# t84.net
KiCad netlist of a schematic drawn in EAGLE
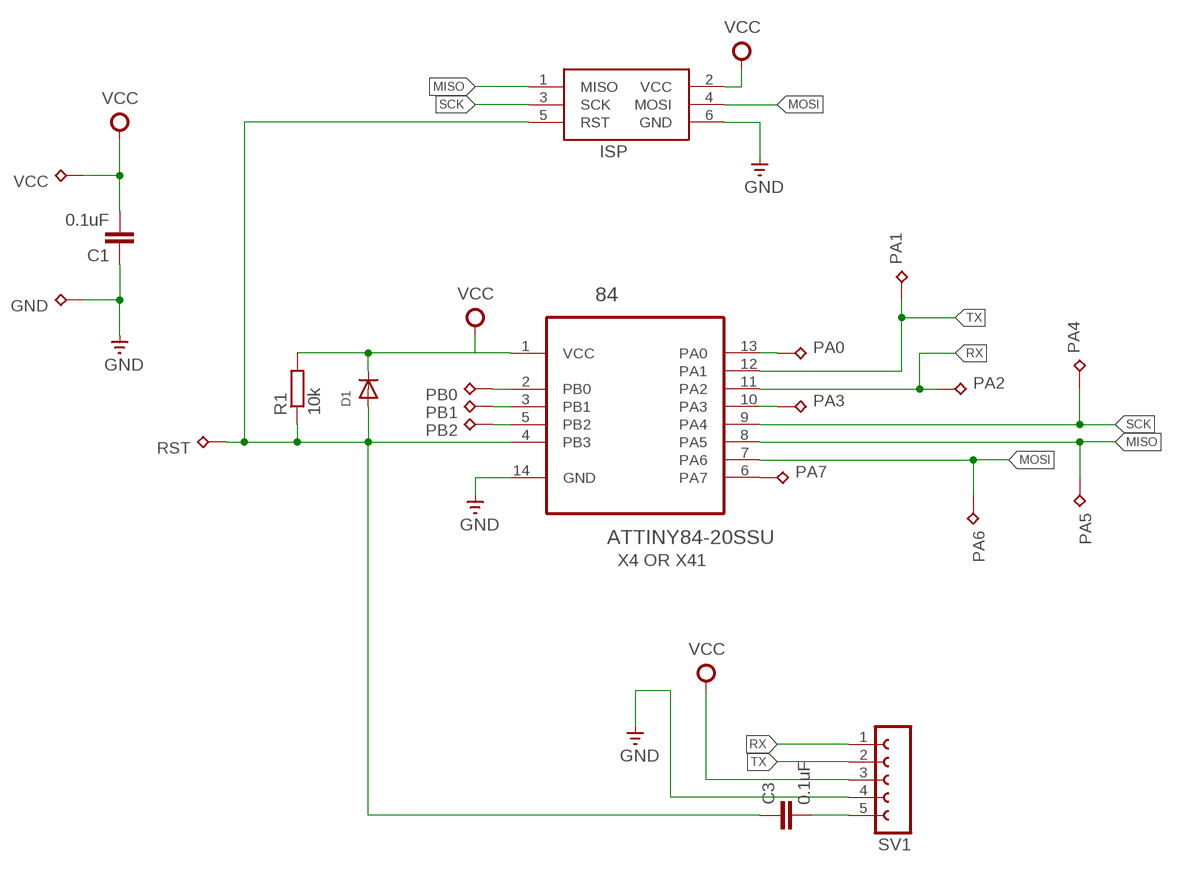
[diagram p0: schematic, sheet 1]

(export (version "E")
  (design (tool "Eeschema 10.0.6"))
  (components
    (comp (ref "84")
      (value "ATTINY84-20SSU")
      (footprint "eagle-import:SOIC127P600X175-14N")
      (libsource (lib "eagle-import") (part "ATTINY84-20SSU"))
    )
    (comp (ref "C1")
      (value "0.1uF")
      (footprint "eagle-import:C0805K")
      (libsource (lib "eagle-import") (part "C-EUC0805K"))
    )
    (comp (ref "C3")
      (value "0.1uF")
      (footprint "eagle-import:C0805K")
      (libsource (lib "eagle-import") (part "C-EUC0805K"))
    )
    (comp (ref "D1")
      (value "DIODESOD-123")
      (footprint "eagle-import:SOD-123")
      (libsource (lib "eagle-import") (part "DIODESOD-123"))
    )
    (comp (ref "GND")
      (value "1XPIN-HEADER")
      (footprint "eagle-import:1XPIN-HEADER")
      (libsource (lib "eagle-import") (part "1XPIN-HEADER"))
    )
    (comp (ref "ISP")
      (value "AVRISP-6")
      (footprint "eagle-import:AVRISP")
      (libsource (lib "eagle-import") (part "AVRISP-6"))
    )
    (comp (ref "PA0")
      (value "1XPIN-HEADER")
      (footprint "eagle-import:1XPIN-HEADER")
      (libsource (lib "eagle-import") (part "1XPIN-HEADER"))
    )
    (comp (ref "PA1")
      (value "1XPIN-HEADER")
      (footprint "eagle-import:1XPIN-HEADER")
      (libsource (lib "eagle-import") (part "1XPIN-HEADER"))
    )
    (comp (ref "PA2")
      (value "1XPIN-HEADER")
      (footprint "eagle-import:1XPIN-HEADER")
      (libsource (lib "eagle-import") (part "1XPIN-HEADER"))
    )
    (comp (ref "PA3")
      (value "1XPIN-HEADER")
      (footprint "eagle-import:1XPIN-HEADER")
      (libsource (lib "eagle-import") (part "1XPIN-HEADER"))
    )
    (comp (ref "PA4")
      (value "1XPIN-HEADER")
      (footprint "eagle-import:1XPIN-HEADER")
      (libsource (lib "eagle-import") (part "1XPIN-HEADER"))
    )
    (comp (ref "PA5")
      (value "1XPIN-HEADER")
      (footprint "eagle-import:1XPIN-HEADER")
      (libsource (lib "eagle-import") (part "1XPIN-HEADER"))
    )
    (comp (ref "PA6")
      (value "1XPIN-HEADER")
      (footprint "eagle-import:1XPIN-HEADER")
      (libsource (lib "eagle-import") (part "1XPIN-HEADER"))
    )
    (comp (ref "PA7")
      (value "1XPIN-HEADER")
      (footprint "eagle-import:1XPIN-HEADER")
      (libsource (lib "eagle-import") (part "1XPIN-HEADER"))
    )
    (comp (ref "PB0")
      (value "1XPIN-HEADER")
      (footprint "eagle-import:1XPIN-HEADER")
      (libsource (lib "eagle-import") (part "1XPIN-HEADER"))
    )
    (comp (ref "PB1")
      (value "1XPIN-HEADER")
      (footprint "eagle-import:1XPIN-HEADER")
      (libsource (lib "eagle-import") (part "1XPIN-HEADER"))
    )
    (comp (ref "PB2")
      (value "1XPIN-HEADER")
      (footprint "eagle-import:1XPIN-HEADER")
      (libsource (lib "eagle-import") (part "1XPIN-HEADER"))
    )
    (comp (ref "R1")
      (value "10k")
      (footprint "eagle-import:M0805")
      (libsource (lib "eagle-import") (part "R-EU_M0805"))
    )
    (comp (ref "RST")
      (value "1XPIN-HEADER")
      (footprint "eagle-import:1XPIN-HEADER")
      (libsource (lib "eagle-import") (part "1XPIN-HEADER"))
    )
    (comp (ref "SV1")
      (value "FE05-1")
      (footprint "eagle-import:FE05-1")
      (libsource (lib "eagle-import") (part "FE05-1"))
    )
    (comp (ref "VCC")
      (value "1XPIN-HEADER")
      (footprint "eagle-import:1XPIN-HEADER")
      (libsource (lib "eagle-import") (part "1XPIN-HEADER"))
    )
  )
  (nets
    (net (code "1") (name "GND") (class "Default")
      (node (ref "84") (pin "14") (pinfunction "GND_14") (pintype "passive"))
      (node (ref "C1") (pin "1") (pinfunction "1_1") (pintype "passive"))
      (node (ref "GND") (pin "P$1") (pinfunction "P$1_P$1") (pintype "bidirectional"))
      (node (ref "ISP") (pin "6") (pinfunction "GND_6") (pintype "power_in"))
      (node (ref "SV1") (pin "4") (pinfunction "4_4") (pintype "passive"))
    )
    (net (code "2") (name "MISO") (class "Default")
      (node (ref "84") (pin "8") (pinfunction "PA5_8") (pintype "bidirectional"))
      (node (ref "ISP") (pin "1") (pinfunction "MISO_1") (pintype "input"))
      (node (ref "PA5") (pin "P$1") (pinfunction "P$1_P$1") (pintype "bidirectional"))
    )
    (net (code "3") (name "MOSI") (class "Default")
      (node (ref "84") (pin "7") (pinfunction "PA6_7") (pintype "bidirectional"))
      (node (ref "ISP") (pin "4") (pinfunction "MOSI_4") (pintype "output"))
      (node (ref "PA6") (pin "P$1") (pinfunction "P$1_P$1") (pintype "bidirectional"))
    )
    (net (code "4") (name "Net-(84-PA0)") (class "Default")
      (node (ref "84") (pin "13") (pinfunction "PA0_13") (pintype "bidirectional"))
      (node (ref "PA0") (pin "P$1") (pinfunction "P$1_P$1") (pintype "bidirectional"))
    )
    (net (code "5") (name "Net-(84-PA3)") (class "Default")
      (node (ref "84") (pin "10") (pinfunction "PA3_10") (pintype "bidirectional"))
      (node (ref "PA3") (pin "P$1") (pinfunction "P$1_P$1") (pintype "bidirectional"))
    )
    (net (code "6") (name "Net-(84-PA7)") (class "Default")
      (node (ref "84") (pin "6") (pinfunction "PA7_6") (pintype "bidirectional"))
      (node (ref "PA7") (pin "P$1") (pinfunction "P$1_P$1") (pintype "bidirectional"))
    )
    (net (code "7") (name "Net-(84-PB0)") (class "Default")
      (node (ref "84") (pin "2") (pinfunction "PB0_2") (pintype "bidirectional"))
      (node (ref "PB0") (pin "P$1") (pinfunction "P$1_P$1") (pintype "bidirectional"))
    )
    (net (code "8") (name "Net-(84-PB1)") (class "Default")
      (node (ref "84") (pin "3") (pinfunction "PB1_3") (pintype "bidirectional"))
      (node (ref "PB1") (pin "P$1") (pinfunction "P$1_P$1") (pintype "bidirectional"))
    )
    (net (code "9") (name "Net-(84-PB2)") (class "Default")
      (node (ref "84") (pin "5") (pinfunction "PB2_5") (pintype "bidirectional"))
      (node (ref "PB2") (pin "P$1") (pinfunction "P$1_P$1") (pintype "bidirectional"))
    )
    (net (code "10") (name "Net-(84-PB3)") (class "Default")
      (node (ref "84") (pin "4") (pinfunction "PB3_4") (pintype "bidirectional"))
      (node (ref "C3") (pin "1") (pinfunction "1_1") (pintype "passive"))
      (node (ref "D1") (pin "A") (pinfunction "A_A") (pintype "passive"))
      (node (ref "ISP") (pin "5") (pinfunction "RST_5") (pintype "output"))
      (node (ref "R1") (pin "1") (pinfunction "1_1") (pintype "passive"))
      (node (ref "RST") (pin "P$1") (pinfunction "P$1_P$1") (pintype "bidirectional"))
    )
    (net (code "11") (name "Net-(C3-Pad2)") (class "Default")
      (node (ref "C3") (pin "2") (pinfunction "2_2") (pintype "passive"))
      (node (ref "SV1") (pin "5") (pinfunction "5_5") (pintype "passive"))
    )
    (net (code "12") (name "RX") (class "Default")
      (node (ref "84") (pin "11") (pinfunction "PA2_11") (pintype "bidirectional"))
      (node (ref "PA2") (pin "P$1") (pinfunction "P$1_P$1") (pintype "bidirectional"))
      (node (ref "SV1") (pin "1") (pinfunction "1_1") (pintype "passive"))
    )
    (net (code "13") (name "SCK") (class "Default")
      (node (ref "84") (pin "9") (pinfunction "PA4_9") (pintype "bidirectional"))
      (node (ref "ISP") (pin "3") (pinfunction "SCK_3") (pintype "output"))
      (node (ref "PA4") (pin "P$1") (pinfunction "P$1_P$1") (pintype "bidirectional"))
    )
    (net (code "14") (name "TX") (class "Default")
      (node (ref "84") (pin "12") (pinfunction "PA1_12") (pintype "bidirectional"))
      (node (ref "PA1") (pin "P$1") (pinfunction "P$1_P$1") (pintype "bidirectional"))
      (node (ref "SV1") (pin "2") (pinfunction "2_2") (pintype "passive"))
    )
    (net (code "15") (name "VCC") (class "Default")
      (node (ref "84") (pin "1") (pinfunction "VCC_1") (pintype "power_in"))
      (node (ref "C1") (pin "2") (pinfunction "2_2") (pintype "passive"))
      (node (ref "D1") (pin "C") (pinfunction "C_C") (pintype "passive"))
      (node (ref "ISP") (pin "2") (pinfunction "VCC_2") (pintype "power_in"))
      (node (ref "R1") (pin "2") (pinfunction "2_2") (pintype "passive"))
      (node (ref "SV1") (pin "3") (pinfunction "3_3") (pintype "passive"))
      (node (ref "VCC") (pin "P$1") (pinfunction "P$1_P$1") (pintype "bidirectional"))
    )
  )
)
